# SparkFun_6DoF_ISM330DHCX.net
KiCad netlist of a schematic drawn in EAGLE
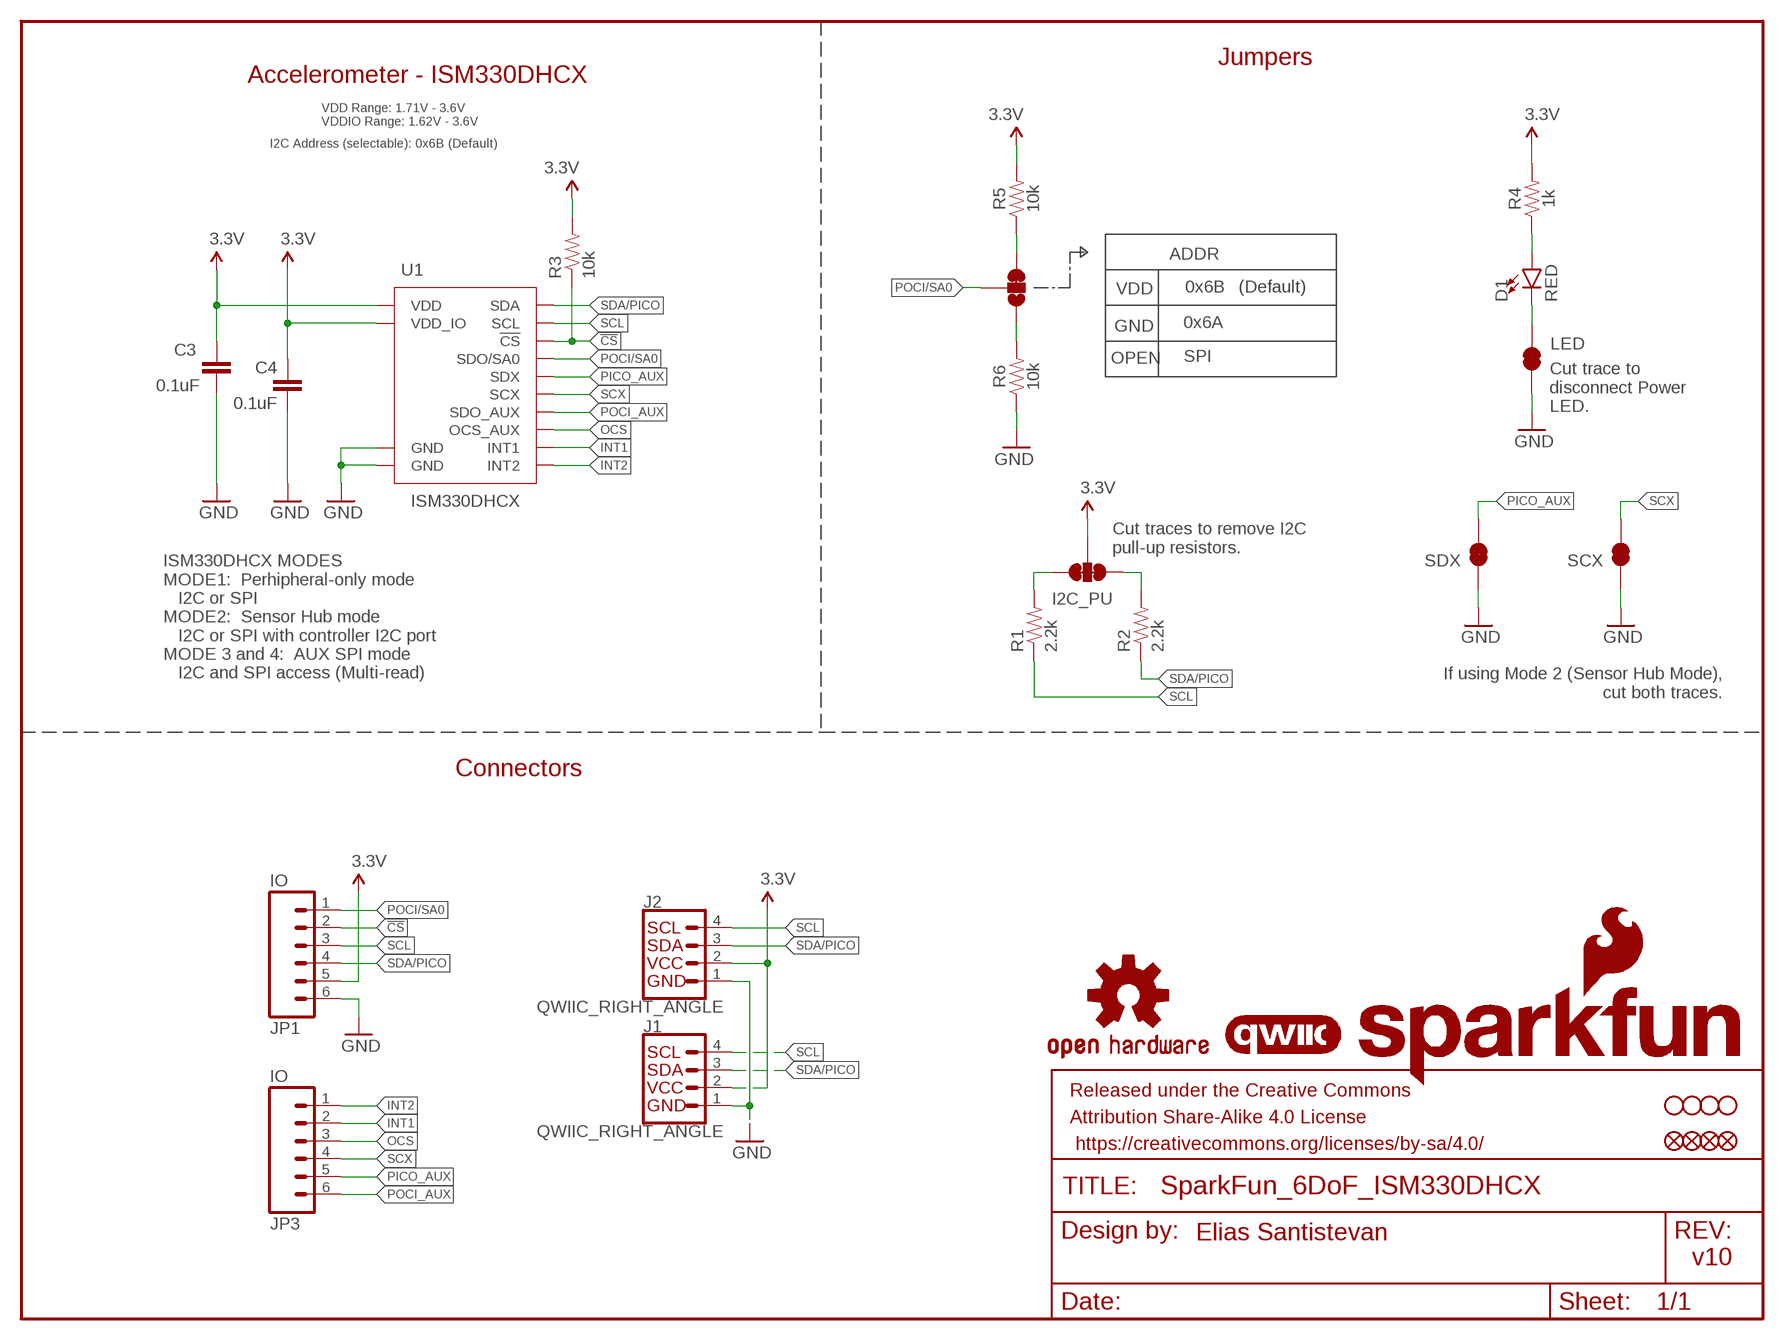
[diagram p0: schematic, sheet 1]

(export (version "E")
  (design (tool "Eeschema 10.0.6"))
  (components
    (comp (ref "ADDR")
      (value "JUMPER-SMT_3_1-NC_TRACE_SILK")
      (footprint "eagle-import:SMT-JUMPER_3_1-NC_TRACE_SILK")
      (libsource (lib "eagle-import") (part "JUMPER-SMT_3_1-NC_TRACE_SILK"))
    )
    (comp (ref "C3")
      (value "0.1uF")
      (footprint "eagle-import:0603")
      (libsource (lib "eagle-import") (part "0.1UF-0603-25V-(+80/-20%)"))
    )
    (comp (ref "C4")
      (value "0.1uF")
      (footprint "eagle-import:0603")
      (libsource (lib "eagle-import") (part "0.1UF-0603-25V-(+80/-20%)"))
    )
    (comp (ref "D1")
      (value "RED")
      (footprint "eagle-import:LED-0603")
      (libsource (lib "eagle-import") (part "LED-RED0603"))
    )
    (comp (ref "FD1")
      (value "FIDUCIALUFIDUCIAL")
      (footprint "eagle-import:FIDUCIAL-MICRO")
      (libsource (lib "eagle-import") (part "FIDUCIALUFIDUCIAL"))
    )
    (comp (ref "FD2")
      (value "FIDUCIALUFIDUCIAL")
      (footprint "eagle-import:FIDUCIAL-MICRO")
      (libsource (lib "eagle-import") (part "FIDUCIALUFIDUCIAL"))
    )
    (comp (ref "FID1")
      (value "FIDUCIALUFIDUCIAL")
      (footprint "eagle-import:FIDUCIAL-MICRO")
      (libsource (lib "eagle-import") (part "FIDUCIALUFIDUCIAL"))
    )
    (comp (ref "FID2")
      (value "FIDUCIALUFIDUCIAL")
      (footprint "eagle-import:FIDUCIAL-MICRO")
      (libsource (lib "eagle-import") (part "FIDUCIALUFIDUCIAL"))
    )
    (comp (ref "FRAME1")
      (value "FRAME-LETTER")
      (footprint "eagle-import:CREATIVE_COMMONS")
      (fields (field (name "DESIGNER") "Elias Santistevan"))
      (libsource (lib "eagle-import") (part "FRAME-LETTER"))
    )
    (comp (ref "I2C_PU")
      (value "S_MODE")
      (footprint "eagle-import:SMT-JUMPER_3_2-NC_TRACE_SILK")
      (libsource (lib "eagle-import") (part "JUMPER-SMT_3_2-NC_TRACE_SILK"))
    )
    (comp (ref "J1")
      (value "QWIIC_RIGHT_ANGLE")
      (footprint "eagle-import:JST04_1MM_RA")
      (libsource (lib "eagle-import") (part "QWIIC_CONNECTORJS-1MM"))
    )
    (comp (ref "J2")
      (value "QWIIC_RIGHT_ANGLE")
      (footprint "eagle-import:JST04_1MM_RA")
      (libsource (lib "eagle-import") (part "QWIIC_CONNECTORJS-1MM"))
    )
    (comp (ref "JP1")
      (value "IO")
      (footprint "eagle-import:1X06_NO_SILK")
      (libsource (lib "eagle-import") (part "CONN_06NO_SILK_NO_POP"))
    )
    (comp (ref "JP3")
      (value "IO")
      (footprint "eagle-import:1X06_NO_SILK")
      (libsource (lib "eagle-import") (part "CONN_06NO_SILK_NO_POP"))
    )
    (comp (ref "LED")
      (value "JUMPER-SMT_2_NC_TRACE_SILK")
      (footprint "eagle-import:SMT-JUMPER_2_NC_TRACE_SILK")
      (libsource (lib "eagle-import") (part "JUMPER-SMT_2_NC_TRACE_SILK"))
    )
    (comp (ref "LOGO1")
      (value "QWIIC_LOGO_4MM")
      (footprint "eagle-import:QWIIC_4MM")
      (libsource (lib "eagle-import") (part "QWIIC_LOGO_4MM"))
    )
    (comp (ref "LOGO2")
      (value "OSHW-LOGOMINI")
      (footprint "eagle-import:OSHW-LOGO-MINI")
      (libsource (lib "eagle-import") (part "OSHW-LOGOMINI"))
    )
    (comp (ref "LOGO3")
      (value "SFE_LOGO_NAME_FLAME.1_INCH")
      (footprint "eagle-import:SFE_LOGO_NAME_FLAME_.1")
      (libsource (lib "eagle-import") (part "SFE_LOGO_NAME_FLAME.1_INCH"))
    )
    (comp (ref "R1")
      (value "2.2k")
      (footprint "eagle-import:0603")
      (libsource (lib "eagle-import") (part "2.2KOHM-0603-1/10W-1%"))
    )
    (comp (ref "R2")
      (value "2.2k")
      (footprint "eagle-import:0603")
      (libsource (lib "eagle-import") (part "2.2KOHM-0603-1/10W-1%"))
    )
    (comp (ref "R3")
      (value "10k")
      (footprint "eagle-import:0603")
      (libsource (lib "eagle-import") (part "10KOHM-0603-1/10W-1%"))
    )
    (comp (ref "R4")
      (value "1k")
      (footprint "eagle-import:0603")
      (libsource (lib "eagle-import") (part "1KOHM-0603-1/10W-1%"))
    )
    (comp (ref "R5")
      (value "10k")
      (footprint "eagle-import:0603")
      (libsource (lib "eagle-import") (part "10KOHM-0603-1/10W-1%"))
    )
    (comp (ref "R6")
      (value "10k")
      (footprint "eagle-import:0603")
      (libsource (lib "eagle-import") (part "10KOHM-0603-1/10W-1%"))
    )
    (comp (ref "SCX")
      (value "JUMPER-SMT_2_NC_TRACE_SILK")
      (footprint "eagle-import:SMT-JUMPER_2_NC_TRACE_SILK")
      (libsource (lib "eagle-import") (part "JUMPER-SMT_2_NC_TRACE_SILK"))
    )
    (comp (ref "SDX")
      (value "JUMPER-SMT_2_NC_TRACE_SILK")
      (footprint "eagle-import:SMT-JUMPER_2_NC_TRACE_SILK")
      (libsource (lib "eagle-import") (part "JUMPER-SMT_2_NC_TRACE_SILK"))
    )
    (comp (ref "STANDOFF1")
      (value "STAND-OFFTIGHT")
      (footprint "eagle-import:STAND-OFF-TIGHT")
      (libsource (lib "eagle-import") (part "STAND-OFFTIGHT"))
    )
    (comp (ref "STANDOFF2")
      (value "STAND-OFFTIGHT")
      (footprint "eagle-import:STAND-OFF-TIGHT")
      (libsource (lib "eagle-import") (part "STAND-OFFTIGHT"))
    )
    (comp (ref "STANDOFF3")
      (value "STAND-OFFTIGHT")
      (footprint "eagle-import:STAND-OFF-TIGHT")
      (libsource (lib "eagle-import") (part "STAND-OFFTIGHT"))
    )
    (comp (ref "STANDOFF4")
      (value "STAND-OFFTIGHT")
      (footprint "eagle-import:STAND-OFF-TIGHT")
      (libsource (lib "eagle-import") (part "STAND-OFFTIGHT"))
    )
    (comp (ref "U1")
      (value "ISM330DHCX")
      (footprint "eagle-import:LGA-14L")
      (libsource (lib "eagle-import") (part "ISM330DHCX"))
    )
  )
  (nets
    (net (code "1") (name "/~{CS}") (class "Default")
      (node (ref "JP1") (pin "2") (pinfunction "2_2") (pintype "passive"))
      (node (ref "R3") (pin "1") (pinfunction "1_1") (pintype "passive"))
      (node (ref "U1") (pin "P12") (pinfunction "~{CS}_P12") (pintype "bidirectional"))
    )
    (net (code "2") (name "3.3V") (class "Default")
      (node (ref "C3") (pin "1") (pinfunction "1_1") (pintype "passive"))
      (node (ref "C4") (pin "1") (pinfunction "1_1") (pintype "passive"))
      (node (ref "I2C_PU") (pin "2") (pinfunction "2_2") (pintype "passive"))
      (node (ref "J1") (pin "2") (pinfunction "2_2") (pintype "power_in"))
      (node (ref "J2") (pin "2") (pinfunction "2_2") (pintype "power_in"))
      (node (ref "JP1") (pin "5") (pinfunction "5_5") (pintype "passive"))
      (node (ref "R3") (pin "2") (pinfunction "2_2") (pintype "passive"))
      (node (ref "R4") (pin "2") (pinfunction "2_2") (pintype "passive"))
      (node (ref "R5") (pin "2") (pinfunction "2_2") (pintype "passive"))
      (node (ref "U1") (pin "P5") (pinfunction "VDD_IO_P5") (pintype "power_in"))
      (node (ref "U1") (pin "P8") (pinfunction "VDD_P8") (pintype "power_in"))
    )
    (net (code "3") (name "GND") (class "Default")
      (node (ref "C3") (pin "2") (pinfunction "2_2") (pintype "passive"))
      (node (ref "C4") (pin "2") (pinfunction "2_2") (pintype "passive"))
      (node (ref "J1") (pin "1") (pinfunction "1_1") (pintype "power_in"))
      (node (ref "J2") (pin "1") (pinfunction "1_1") (pintype "power_in"))
      (node (ref "JP1") (pin "6") (pinfunction "6_6") (pintype "passive"))
      (node (ref "LED") (pin "1") (pinfunction "1_1") (pintype "passive"))
      (node (ref "R6") (pin "1") (pinfunction "1_1") (pintype "passive"))
      (node (ref "SCX") (pin "1") (pinfunction "1_1") (pintype "passive"))
      (node (ref "SDX") (pin "1") (pinfunction "1_1") (pintype "passive"))
      (node (ref "U1") (pin "P6") (pinfunction "GND_P6") (pintype "power_in"))
      (node (ref "U1") (pin "P7") (pinfunction "GND_P7") (pintype "power_in"))
    )
    (net (code "4") (name "INT1") (class "Default")
      (node (ref "JP3") (pin "2") (pinfunction "2_2") (pintype "passive"))
      (node (ref "U1") (pin "P4") (pinfunction "INT1_P4") (pintype "bidirectional"))
    )
    (net (code "5") (name "INT2") (class "Default")
      (node (ref "JP3") (pin "1") (pinfunction "1_1") (pintype "passive"))
      (node (ref "U1") (pin "P9") (pinfunction "INT2_P9") (pintype "bidirectional"))
    )
    (net (code "6") (name "Net-(ADDR-Pad1)") (class "Default")
      (node (ref "ADDR") (pin "1") (pinfunction "1_1") (pintype "passive"))
      (node (ref "R6") (pin "2") (pinfunction "2_2") (pintype "passive"))
    )
    (net (code "7") (name "Net-(ADDR-Pad3)") (class "Default")
      (node (ref "ADDR") (pin "3") (pinfunction "3_3") (pintype "passive"))
      (node (ref "R5") (pin "1") (pinfunction "1_1") (pintype "passive"))
    )
    (net (code "8") (name "Net-(D1-PadA)") (class "Default")
      (node (ref "D1") (pin "A") (pinfunction "A_A") (pintype "passive"))
      (node (ref "R4") (pin "1") (pinfunction "1_1") (pintype "passive"))
    )
    (net (code "9") (name "Net-(D1-PadC)") (class "Default")
      (node (ref "D1") (pin "C") (pinfunction "C_C") (pintype "passive"))
      (node (ref "LED") (pin "2") (pinfunction "2_2") (pintype "passive"))
    )
    (net (code "10") (name "Net-(I2C_PU-Pad1)") (class "Default")
      (node (ref "I2C_PU") (pin "1") (pinfunction "1_1") (pintype "passive"))
      (node (ref "R1") (pin "2") (pinfunction "2_2") (pintype "passive"))
    )
    (net (code "11") (name "Net-(I2C_PU-Pad3)") (class "Default")
      (node (ref "I2C_PU") (pin "3") (pinfunction "3_3") (pintype "passive"))
      (node (ref "R2") (pin "2") (pinfunction "2_2") (pintype "passive"))
    )
    (net (code "12") (name "OCS") (class "Default")
      (node (ref "JP3") (pin "3") (pinfunction "3_3") (pintype "passive"))
      (node (ref "U1") (pin "P10") (pinfunction "OCS_AUX_P10") (pintype "bidirectional"))
    )
    (net (code "13") (name "PICO_AUX") (class "Default")
      (node (ref "JP3") (pin "5") (pinfunction "5_5") (pintype "passive"))
      (node (ref "SDX") (pin "2") (pinfunction "2_2") (pintype "passive"))
      (node (ref "U1") (pin "P2") (pinfunction "SDX_P2") (pintype "bidirectional"))
    )
    (net (code "14") (name "POCI_AUX") (class "Default")
      (node (ref "JP3") (pin "6") (pinfunction "6_6") (pintype "passive"))
      (node (ref "U1") (pin "P11") (pinfunction "SDO_AUX_P11") (pintype "bidirectional"))
    )
    (net (code "15") (name "POCI{slash}SA0") (class "Default")
      (node (ref "ADDR") (pin "2") (pinfunction "2_2") (pintype "passive"))
      (node (ref "JP1") (pin "1") (pinfunction "1_1") (pintype "passive"))
      (node (ref "U1") (pin "P1") (pinfunction "SDO/SA0_P1") (pintype "bidirectional"))
    )
    (net (code "16") (name "SCL") (class "Default")
      (node (ref "J1") (pin "4") (pinfunction "4_4") (pintype "passive"))
      (node (ref "J2") (pin "4") (pinfunction "4_4") (pintype "passive"))
      (node (ref "JP1") (pin "3") (pinfunction "3_3") (pintype "passive"))
      (node (ref "R1") (pin "1") (pinfunction "1_1") (pintype "passive"))
      (node (ref "U1") (pin "P13") (pinfunction "SCL_P13") (pintype "bidirectional"))
    )
    (net (code "17") (name "SCX") (class "Default")
      (node (ref "JP3") (pin "4") (pinfunction "4_4") (pintype "passive"))
      (node (ref "SCX") (pin "2") (pinfunction "2_2") (pintype "passive"))
      (node (ref "U1") (pin "P3") (pinfunction "SCX_P3") (pintype "bidirectional"))
    )
    (net (code "18") (name "SDA{slash}PICO") (class "Default")
      (node (ref "J1") (pin "3") (pinfunction "3_3") (pintype "passive"))
      (node (ref "J2") (pin "3") (pinfunction "3_3") (pintype "passive"))
      (node (ref "JP1") (pin "4") (pinfunction "4_4") (pintype "passive"))
      (node (ref "R2") (pin "1") (pinfunction "1_1") (pintype "passive"))
      (node (ref "U1") (pin "P14") (pinfunction "SDA_P14") (pintype "bidirectional"))
    )
  )
)
